# TK106_MIDI.net
KiCad netlist of a schematic drawn in Altium Designer
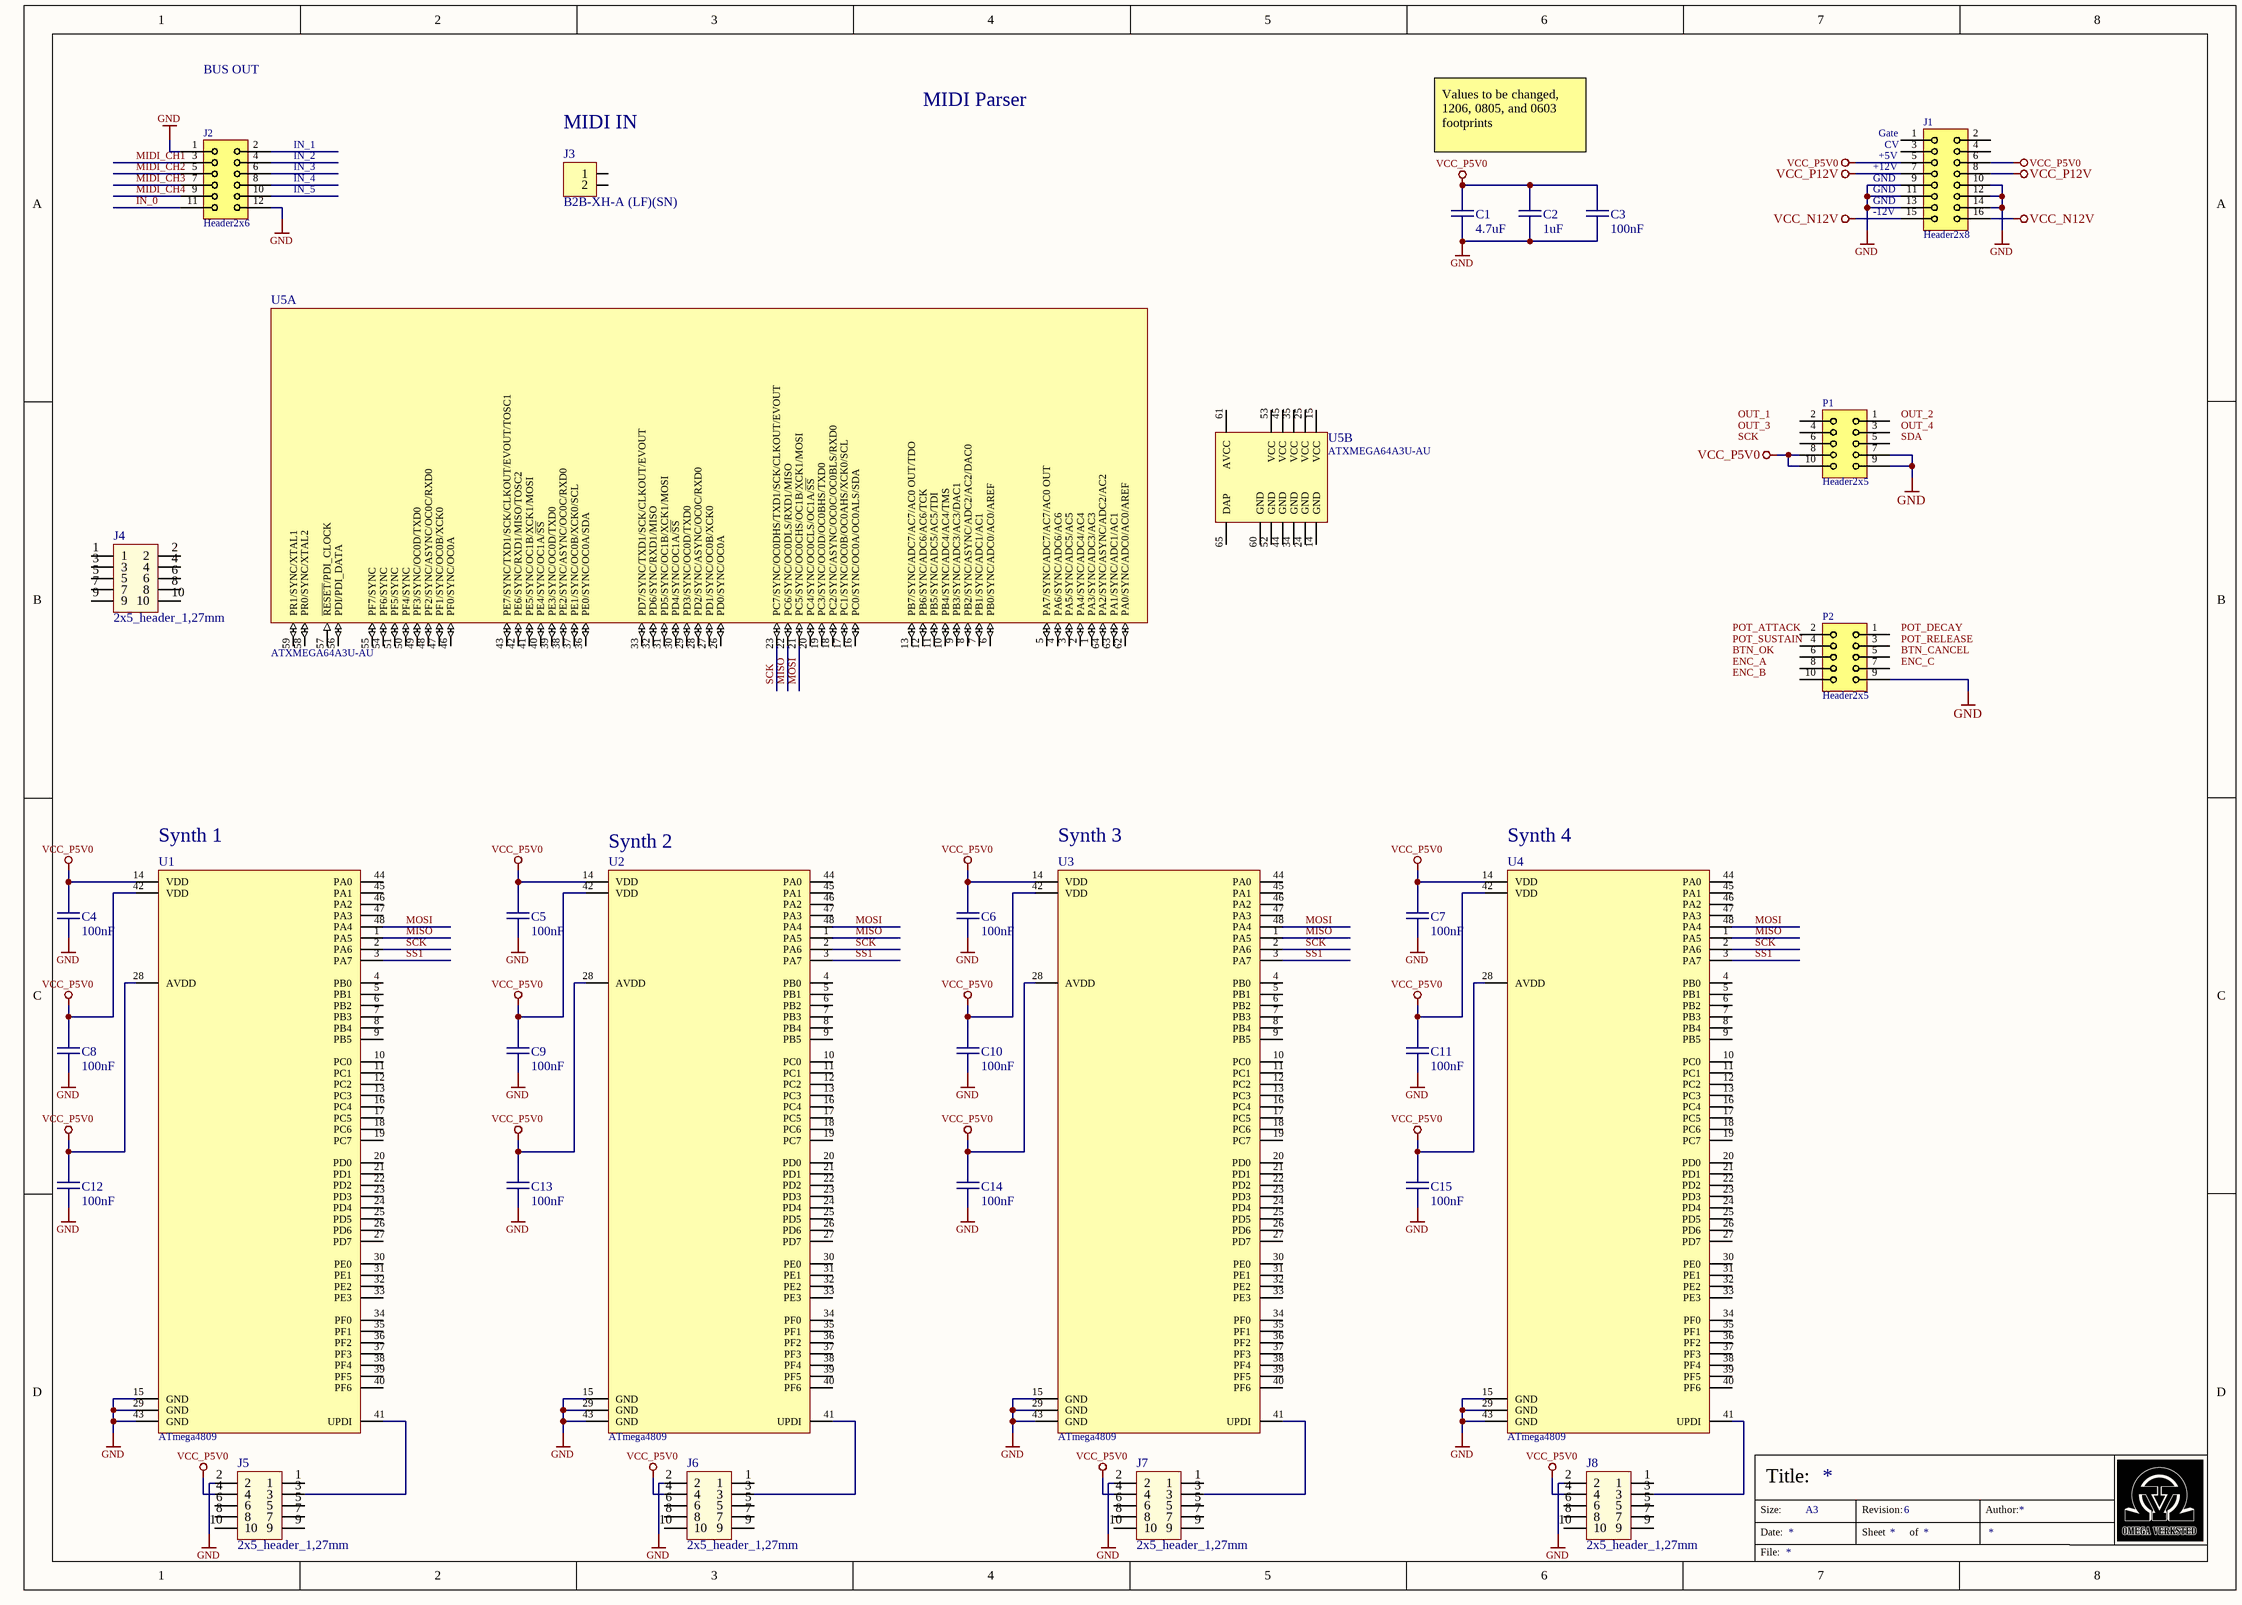
[diagram p0: TK106_MIDI.SchDoc]

(export (version "E")
  (design (tool "Eeschema 10.0.6"))
  (components
    (comp (ref "C1")
      (value "4.7uF")
      (footprint "CAPC1206(3216)170_N")
      (description "X7R 50V")
      (libsource (lib "OVLib") (part "CAP"))
    )
    (comp (ref "C2")
      (value "1uF")
      (footprint "CAPC0805(2012)100_N")
      (description "X7R 50V 10%")
      (libsource (lib "OVLib") (part "CAP"))
    )
    (comp (ref "C3")
      (value "100nF")
      (footprint "CAPC0603(1608)55_N")
      (description "X7R 50V 5%")
      (libsource (lib "OVLib") (part "CAP"))
    )
    (comp (ref "C4")
      (value "100nF")
      (footprint "CAPC0603(1608)55_N")
      (description "X7R 50V 5%")
      (libsource (lib "OVLib_64") (part "CAP"))
    )
    (comp (ref "C5")
      (value "100nF")
      (footprint "CAPC0603(1608)55_N")
      (description "X7R 50V 5%")
      (libsource (lib "OVLib_64") (part "CAP"))
    )
    (comp (ref "C6")
      (value "100nF")
      (footprint "CAPC0603(1608)55_N")
      (description "X7R 50V 5%")
      (libsource (lib "OVLib_64") (part "CAP"))
    )
    (comp (ref "C7")
      (value "100nF")
      (footprint "CAPC0603(1608)55_N")
      (description "X7R 50V 5%")
      (libsource (lib "OVLib_64") (part "CAP"))
    )
    (comp (ref "C8")
      (value "100nF")
      (footprint "CAPC0603(1608)55_N")
      (description "X7R 50V 5%")
      (libsource (lib "OVLib_64") (part "CAP"))
    )
    (comp (ref "C9")
      (value "100nF")
      (footprint "CAPC0603(1608)55_N")
      (description "X7R 50V 5%")
      (libsource (lib "OVLib_64") (part "CAP"))
    )
    (comp (ref "C10")
      (value "100nF")
      (footprint "CAPC0603(1608)55_N")
      (description "X7R 50V 5%")
      (libsource (lib "OVLib_64") (part "CAP"))
    )
    (comp (ref "C11")
      (value "100nF")
      (footprint "CAPC0603(1608)55_N")
      (description "X7R 50V 5%")
      (libsource (lib "OVLib_64") (part "CAP"))
    )
    (comp (ref "C12")
      (value "100nF")
      (footprint "CAPC0603(1608)55_N")
      (description "X7R 50V 5%")
      (libsource (lib "OVLib_64") (part "CAP"))
    )
    (comp (ref "C13")
      (value "100nF")
      (footprint "CAPC0603(1608)55_N")
      (description "X7R 50V 5%")
      (libsource (lib "OVLib_64") (part "CAP"))
    )
    (comp (ref "C14")
      (value "100nF")
      (footprint "CAPC0603(1608)55_N")
      (description "X7R 50V 5%")
      (libsource (lib "OVLib_64") (part "CAP"))
    )
    (comp (ref "C15")
      (value "100nF")
      (footprint "CAPC0603(1608)55_N")
      (description "X7R 50V 5%")
      (libsource (lib "OVLib_64") (part "CAP"))
    )
    (comp (ref "J1")
      (value "Header2x8")
      (footprint "HDRV16W64P254_2X8_Shrouded")
      (libsource (lib "OVLib_64") (part "Header2x8"))
    )
    (comp (ref "J2")
      (value "Header2x6")
      (footprint "HDRV12W64P254_2X6_Shrouded")
      (libsource (lib "OVLib_64") (part "Header2x6"))
    )
    (comp (ref "J3")
      (value "B2B-XH-A (LF)(SN)")
      (footprint "JST_2P")
      (libsource (lib "OVLib_64") (part "2PConnector"))
    )
    (comp (ref "J4")
      (value "2x5_header_1,27mm")
      (footprint "SMDHDRV10P127_2X5_615X330X560B")
      (libsource (lib "") (part "2x5_header_1,27mm_1"))
    )
    (comp (ref "J5")
      (value "2x5_header_1,27mm")
      (footprint "SMDHDRV10P127_2X5_615X330X560B")
      (libsource (lib "OVLib_64") (part "2x5_header_1,27mm"))
    )
    (comp (ref "J6")
      (value "2x5_header_1,27mm")
      (footprint "SMDHDRV10P127_2X5_615X330X560B")
      (libsource (lib "OVLib_64") (part "2x5_header_1,27mm"))
    )
    (comp (ref "J7")
      (value "2x5_header_1,27mm")
      (footprint "SMDHDRV10P127_2X5_615X330X560B")
      (libsource (lib "OVLib_64") (part "2x5_header_1,27mm"))
    )
    (comp (ref "J8")
      (value "2x5_header_1,27mm")
      (footprint "SMDHDRV10P127_2X5_615X330X560B")
      (libsource (lib "OVLib_64") (part "2x5_header_1,27mm"))
    )
    (comp (ref "P1")
      (value "Header2x5")
      (footprint "HDRV10W64P254_2X5_Female")
      (libsource (lib "OVLib_64") (part "Header2x5"))
    )
    (comp (ref "P2")
      (value "Header2x5")
      (footprint "HDRV10W64P254_2X5_Female")
      (libsource (lib "OVLib_64") (part "Header2x5"))
    )
    (comp (ref "U1")
      (value "ATmega4809")
      (footprint "TQFP50P900X900X120-48N")
      (libsource (lib "OVLib_64") (part "ATMEGA4809"))
    )
    (comp (ref "U2")
      (value "ATmega4809")
      (footprint "TQFP50P900X900X120-48N")
      (libsource (lib "OVLib_64") (part "ATMEGA4809"))
    )
    (comp (ref "U3")
      (value "ATmega4809")
      (footprint "TQFP50P900X900X120-48N")
      (libsource (lib "OVLib_64") (part "ATMEGA4809"))
    )
    (comp (ref "U4")
      (value "ATmega4809")
      (footprint "TQFP50P900X900X120-48N")
      (libsource (lib "OVLib_64") (part "ATMEGA4809"))
    )
    (comp (ref "U5")
      (value "ATXMEGA64A3U-AU")
      (footprint "TQFP64")
      (libsource (lib "OVLib_64") (part "ATXMEGA-64A3"))
    )
  )
  (nets
    (net (code "6") (name "/IN_0") (class "Default")
      (node (ref "J2") (pin "11") (pinfunction "11_11") (pintype "passive"))
    )
    (net (code "7") (name "/MIDI_CH1") (class "Default")
      (node (ref "J2") (pin "3") (pinfunction "3_3") (pintype "passive"))
    )
    (net (code "8") (name "/MIDI_CH2") (class "Default")
      (node (ref "J2") (pin "5") (pinfunction "5_5") (pintype "passive"))
    )
    (net (code "9") (name "/MIDI_CH3") (class "Default")
      (node (ref "J2") (pin "7") (pinfunction "7_7") (pintype "passive"))
    )
    (net (code "10") (name "/MIDI_CH4") (class "Default")
      (node (ref "J2") (pin "9") (pinfunction "9_9") (pintype "passive"))
    )
    (net (code "11") (name "/MISO") (class "Default")
      (node (ref "U1") (pin "1") (pinfunction "PA5_1") (pintype "passive"))
      (node (ref "U2") (pin "1") (pinfunction "PA5_1") (pintype "passive"))
      (node (ref "U3") (pin "1") (pinfunction "PA5_1") (pintype "passive"))
      (node (ref "U4") (pin "1") (pinfunction "PA5_1") (pintype "passive"))
      (node (ref "U5") (pin "22") (pinfunction "PC6/SYNC/OC0DLS/RXD1/MISO_22") (pintype "bidirectional"))
    )
    (net (code "12") (name "/MOSI") (class "Default")
      (node (ref "U1") (pin "48") (pinfunction "PA4_48") (pintype "passive"))
      (node (ref "U2") (pin "48") (pinfunction "PA4_48") (pintype "passive"))
      (node (ref "U3") (pin "48") (pinfunction "PA4_48") (pintype "passive"))
      (node (ref "U4") (pin "48") (pinfunction "PA4_48") (pintype "passive"))
      (node (ref "U5") (pin "21") (pinfunction "PC5/SYNC/OC0CHS/OC1B/XCK1/MOSI_21") (pintype "bidirectional"))
    )
    (net (code "21") (name "/SCK") (class "Default")
      (node (ref "U1") (pin "2") (pinfunction "PA6_2") (pintype "passive"))
      (node (ref "U2") (pin "2") (pinfunction "PA6_2") (pintype "passive"))
      (node (ref "U3") (pin "2") (pinfunction "PA6_2") (pintype "passive"))
      (node (ref "U4") (pin "2") (pinfunction "PA6_2") (pintype "passive"))
      (node (ref "U5") (pin "23") (pinfunction "PC7/SYNC/OC0DHS/TXD1/SCK/CLKOUT/EVOUT_23") (pintype "bidirectional"))
    )
    (net (code "23") (name "/SS1") (class "Default")
      (node (ref "U1") (pin "3") (pinfunction "PA7_3") (pintype "passive"))
      (node (ref "U2") (pin "3") (pinfunction "PA7_3") (pintype "passive"))
      (node (ref "U3") (pin "3") (pinfunction "PA7_3") (pintype "passive"))
      (node (ref "U4") (pin "3") (pinfunction "PA7_3") (pintype "passive"))
    )
    (net (code "24") (name "GND") (class "Default")
      (node (ref "C1") (pin "1") (pinfunction "1_1") (pintype "passive"))
      (node (ref "C10") (pin "1") (pinfunction "1_1") (pintype "passive"))
      (node (ref "C11") (pin "1") (pinfunction "1_1") (pintype "passive"))
      (node (ref "C12") (pin "1") (pinfunction "1_1") (pintype "passive"))
      (node (ref "C13") (pin "1") (pinfunction "1_1") (pintype "passive"))
      (node (ref "C14") (pin "1") (pinfunction "1_1") (pintype "passive"))
      (node (ref "C15") (pin "1") (pinfunction "1_1") (pintype "passive"))
      (node (ref "C2") (pin "1") (pinfunction "1_1") (pintype "passive"))
      (node (ref "C3") (pin "1") (pinfunction "1_1") (pintype "passive"))
      (node (ref "C4") (pin "1") (pinfunction "1_1") (pintype "passive"))
      (node (ref "C5") (pin "1") (pinfunction "1_1") (pintype "passive"))
      (node (ref "C6") (pin "1") (pinfunction "1_1") (pintype "passive"))
      (node (ref "C7") (pin "1") (pinfunction "1_1") (pintype "passive"))
      (node (ref "C8") (pin "1") (pinfunction "1_1") (pintype "passive"))
      (node (ref "C9") (pin "1") (pinfunction "1_1") (pintype "passive"))
      (node (ref "J1") (pin "10") (pinfunction "10_10") (pintype "passive"))
      (node (ref "J1") (pin "11") (pinfunction "11_11") (pintype "passive"))
      (node (ref "J1") (pin "12") (pinfunction "12_12") (pintype "passive"))
      (node (ref "J1") (pin "13") (pinfunction "13_13") (pintype "passive"))
      (node (ref "J1") (pin "14") (pinfunction "14_14") (pintype "passive"))
      (node (ref "J1") (pin "9") (pinfunction "9_9") (pintype "passive"))
      (node (ref "J2") (pin "1") (pinfunction "1_1") (pintype "passive"))
      (node (ref "J2") (pin "12") (pinfunction "12_12") (pintype "passive"))
      (node (ref "J5") (pin "2") (pinfunction "2_2") (pintype "power_in"))
      (node (ref "J6") (pin "2") (pinfunction "2_2") (pintype "power_in"))
      (node (ref "J7") (pin "2") (pinfunction "2_2") (pintype "power_in"))
      (node (ref "J8") (pin "2") (pinfunction "2_2") (pintype "power_in"))
      (node (ref "P1") (pin "7") (pinfunction "7_7") (pintype "passive"))
      (node (ref "P1") (pin "9") (pinfunction "9_9") (pintype "passive"))
      (node (ref "P2") (pin "9") (pinfunction "9_9") (pintype "passive"))
      (node (ref "U1") (pin "15") (pinfunction "GND_15") (pintype "passive"))
      (node (ref "U1") (pin "29") (pinfunction "GND_29") (pintype "passive"))
      (node (ref "U1") (pin "43") (pinfunction "GND_43") (pintype "passive"))
      (node (ref "U2") (pin "15") (pinfunction "GND_15") (pintype "passive"))
      (node (ref "U2") (pin "29") (pinfunction "GND_29") (pintype "passive"))
      (node (ref "U2") (pin "43") (pinfunction "GND_43") (pintype "passive"))
      (node (ref "U3") (pin "15") (pinfunction "GND_15") (pintype "passive"))
      (node (ref "U3") (pin "29") (pinfunction "GND_29") (pintype "passive"))
      (node (ref "U3") (pin "43") (pinfunction "GND_43") (pintype "passive"))
      (node (ref "U4") (pin "15") (pinfunction "GND_15") (pintype "passive"))
      (node (ref "U4") (pin "29") (pinfunction "GND_29") (pintype "passive"))
      (node (ref "U4") (pin "43") (pinfunction "GND_43") (pintype "passive"))
    )
    (net (code "25") (name "Net-(U1-UPDI)") (class "Default")
      (node (ref "J5") (pin "3") (pinfunction "3_3") (pintype "power_in"))
      (node (ref "U1") (pin "41") (pinfunction "UPDI_41") (pintype "passive"))
    )
    (net (code "26") (name "Net-(U2-UPDI)") (class "Default")
      (node (ref "J6") (pin "3") (pinfunction "3_3") (pintype "power_in"))
      (node (ref "U2") (pin "41") (pinfunction "UPDI_41") (pintype "passive"))
    )
    (net (code "27") (name "Net-(U3-UPDI)") (class "Default")
      (node (ref "J7") (pin "3") (pinfunction "3_3") (pintype "power_in"))
      (node (ref "U3") (pin "41") (pinfunction "UPDI_41") (pintype "passive"))
    )
    (net (code "28") (name "Net-(U4-UPDI)") (class "Default")
      (node (ref "J8") (pin "3") (pinfunction "3_3") (pintype "power_in"))
      (node (ref "U4") (pin "41") (pinfunction "UPDI_41") (pintype "passive"))
    )
    (net (code "29") (name "VCC_N12V") (class "Default")
      (node (ref "J1") (pin "15") (pinfunction "15_15") (pintype "passive"))
      (node (ref "J1") (pin "16") (pinfunction "16_16") (pintype "passive"))
    )
    (net (code "30") (name "VCC_P5V0") (class "Default")
      (node (ref "C1") (pin "2") (pinfunction "2_2") (pintype "passive"))
      (node (ref "C10") (pin "2") (pinfunction "2_2") (pintype "passive"))
      (node (ref "C11") (pin "2") (pinfunction "2_2") (pintype "passive"))
      (node (ref "C12") (pin "2") (pinfunction "2_2") (pintype "passive"))
      (node (ref "C13") (pin "2") (pinfunction "2_2") (pintype "passive"))
      (node (ref "C14") (pin "2") (pinfunction "2_2") (pintype "passive"))
      (node (ref "C15") (pin "2") (pinfunction "2_2") (pintype "passive"))
      (node (ref "C2") (pin "2") (pinfunction "2_2") (pintype "passive"))
      (node (ref "C3") (pin "2") (pinfunction "2_2") (pintype "passive"))
      (node (ref "C4") (pin "2") (pinfunction "2_2") (pintype "passive"))
      (node (ref "C5") (pin "2") (pinfunction "2_2") (pintype "passive"))
      (node (ref "C6") (pin "2") (pinfunction "2_2") (pintype "passive"))
      (node (ref "C7") (pin "2") (pinfunction "2_2") (pintype "passive"))
      (node (ref "C8") (pin "2") (pinfunction "2_2") (pintype "passive"))
      (node (ref "C9") (pin "2") (pinfunction "2_2") (pintype "passive"))
      (node (ref "J1") (pin "5") (pinfunction "5_5") (pintype "passive"))
      (node (ref "J1") (pin "6") (pinfunction "6_6") (pintype "passive"))
      (node (ref "J5") (pin "4") (pinfunction "4_4") (pintype "power_in"))
      (node (ref "J6") (pin "4") (pinfunction "4_4") (pintype "power_in"))
      (node (ref "J7") (pin "4") (pinfunction "4_4") (pintype "power_in"))
      (node (ref "J8") (pin "4") (pinfunction "4_4") (pintype "power_in"))
      (node (ref "P1") (pin "10") (pinfunction "10_10") (pintype "passive"))
      (node (ref "P1") (pin "8") (pinfunction "8_8") (pintype "passive"))
      (node (ref "U1") (pin "14") (pinfunction "VDD_14") (pintype "passive"))
      (node (ref "U1") (pin "28") (pinfunction "AVDD_28") (pintype "passive"))
      (node (ref "U1") (pin "42") (pinfunction "VDD_42") (pintype "passive"))
      (node (ref "U2") (pin "14") (pinfunction "VDD_14") (pintype "passive"))
      (node (ref "U2") (pin "28") (pinfunction "AVDD_28") (pintype "passive"))
      (node (ref "U2") (pin "42") (pinfunction "VDD_42") (pintype "passive"))
      (node (ref "U3") (pin "14") (pinfunction "VDD_14") (pintype "passive"))
      (node (ref "U3") (pin "28") (pinfunction "AVDD_28") (pintype "passive"))
      (node (ref "U3") (pin "42") (pinfunction "VDD_42") (pintype "passive"))
      (node (ref "U4") (pin "14") (pinfunction "VDD_14") (pintype "passive"))
      (node (ref "U4") (pin "28") (pinfunction "AVDD_28") (pintype "passive"))
      (node (ref "U4") (pin "42") (pinfunction "VDD_42") (pintype "passive"))
    )
    (net (code "31") (name "VCC_P12V") (class "Default")
      (node (ref "J1") (pin "7") (pinfunction "7_7") (pintype "passive"))
      (node (ref "J1") (pin "8") (pinfunction "8_8") (pintype "passive"))
    )
    (net (code "32") (name "unconnected-(J1-Pad1)") (class "Default")
      (node (ref "J1") (pin "1") (pinfunction "1_1") (pintype "passive"))
    )
    (net (code "33") (name "unconnected-(J1-Pad2)") (class "Default")
      (node (ref "J1") (pin "2") (pinfunction "2_2") (pintype "passive"))
    )
    (net (code "34") (name "unconnected-(J1-Pad3)") (class "Default")
      (node (ref "J1") (pin "3") (pinfunction "3_3") (pintype "passive"))
    )
    (net (code "35") (name "unconnected-(J1-Pad4)") (class "Default")
      (node (ref "J1") (pin "4") (pinfunction "4_4") (pintype "passive"))
    )
    (net (code "36") (name "unconnected-(J2-Pad2)") (class "Default")
      (node (ref "J2") (pin "2") (pinfunction "2_2") (pintype "passive"))
    )
    (net (code "37") (name "unconnected-(J2-Pad4)") (class "Default")
      (node (ref "J2") (pin "4") (pinfunction "4_4") (pintype "passive"))
    )
    (net (code "38") (name "unconnected-(J2-Pad6)") (class "Default")
      (node (ref "J2") (pin "6") (pinfunction "6_6") (pintype "passive"))
    )
    (net (code "39") (name "unconnected-(J2-Pad8)") (class "Default")
      (node (ref "J2") (pin "8") (pinfunction "8_8") (pintype "passive"))
    )
    (net (code "40") (name "unconnected-(J2-Pad10)") (class "Default")
      (node (ref "J2") (pin "10") (pinfunction "10_10") (pintype "passive"))
    )
    (net (code "41") (name "unconnected-(J3-Pad1)") (class "Default")
      (node (ref "J3") (pin "1") (pinfunction "1_1") (pintype "passive"))
    )
    (net (code "42") (name "unconnected-(J3-Pad2)") (class "Default")
      (node (ref "J3") (pin "2") (pinfunction "2_2") (pintype "passive"))
    )
    (net (code "43") (name "unconnected-(J4-Pad1)") (class "Default")
      (node (ref "J4") (pin "1") (pinfunction "1_1") (pintype "power_in"))
    )
    (net (code "44") (name "unconnected-(J4-Pad2)") (class "Default")
      (node (ref "J4") (pin "2") (pinfunction "2_2") (pintype "power_in"))
    )
    (net (code "45") (name "unconnected-(J4-Pad3)") (class "Default")
      (node (ref "J4") (pin "3") (pinfunction "3_3") (pintype "power_in"))
    )
    (net (code "46") (name "unconnected-(J4-Pad4)") (class "Default")
      (node (ref "J4") (pin "4") (pinfunction "4_4") (pintype "power_in"))
    )
    (net (code "47") (name "unconnected-(J4-Pad5)") (class "Default")
      (node (ref "J4") (pin "5") (pinfunction "5_5") (pintype "power_in"))
    )
    (net (code "48") (name "unconnected-(J4-Pad6)") (class "Default")
      (node (ref "J4") (pin "6") (pinfunction "6_6") (pintype "power_in"))
    )
    (net (code "49") (name "unconnected-(J4-Pad7)") (class "Default")
      (node (ref "J4") (pin "7") (pinfunction "7_7") (pintype "power_in"))
    )
    (net (code "50") (name "unconnected-(J4-Pad8)") (class "Default")
      (node (ref "J4") (pin "8") (pinfunction "8_8") (pintype "power_in"))
    )
    (net (code "51") (name "unconnected-(J4-Pad9)") (class "Default")
      (node (ref "J4") (pin "9") (pinfunction "9_9") (pintype "power_in"))
    )
    (net (code "52") (name "unconnected-(J4-Pad10)") (class "Default")
      (node (ref "J4") (pin "10") (pinfunction "10_10") (pintype "power_in"))
    )
    (net (code "53") (name "unconnected-(J5-Pad1)") (class "Default")
      (node (ref "J5") (pin "1") (pinfunction "1_1") (pintype "power_in"))
    )
    (net (code "54") (name "unconnected-(J5-Pad5)") (class "Default")
      (node (ref "J5") (pin "5") (pinfunction "5_5") (pintype "power_in"))
    )
    (net (code "55") (name "unconnected-(J5-Pad6)") (class "Default")
      (node (ref "J5") (pin "6") (pinfunction "6_6") (pintype "power_in"))
    )
    (net (code "56") (name "unconnected-(J5-Pad7)") (class "Default")
      (node (ref "J5") (pin "7") (pinfunction "7_7") (pintype "power_in"))
    )
    (net (code "57") (name "unconnected-(J5-Pad8)") (class "Default")
      (node (ref "J5") (pin "8") (pinfunction "8_8") (pintype "power_in"))
    )
    (net (code "58") (name "unconnected-(J5-Pad9)") (class "Default")
      (node (ref "J5") (pin "9") (pinfunction "9_9") (pintype "power_in"))
    )
    (net (code "59") (name "unconnected-(J5-Pad10)") (class "Default")
      (node (ref "J5") (pin "10") (pinfunction "10_10") (pintype "power_in"))
    )
    (net (code "60") (name "unconnected-(J6-Pad1)") (class "Default")
      (node (ref "J6") (pin "1") (pinfunction "1_1") (pintype "power_in"))
    )
    (net (code "61") (name "unconnected-(J6-Pad5)") (class "Default")
      (node (ref "J6") (pin "5") (pinfunction "5_5") (pintype "power_in"))
    )
    (net (code "62") (name "unconnected-(J6-Pad6)") (class "Default")
      (node (ref "J6") (pin "6") (pinfunction "6_6") (pintype "power_in"))
    )
    (net (code "63") (name "unconnected-(J6-Pad7)") (class "Default")
      (node (ref "J6") (pin "7") (pinfunction "7_7") (pintype "power_in"))
    )
    (net (code "64") (name "unconnected-(J6-Pad8)") (class "Default")
      (node (ref "J6") (pin "8") (pinfunction "8_8") (pintype "power_in"))
    )
    (net (code "65") (name "unconnected-(J6-Pad9)") (class "Default")
      (node (ref "J6") (pin "9") (pinfunction "9_9") (pintype "power_in"))
    )
    (net (code "66") (name "unconnected-(J6-Pad10)") (class "Default")
      (node (ref "J6") (pin "10") (pinfunction "10_10") (pintype "power_in"))
    )
    (net (code "67") (name "unconnected-(J7-Pad1)") (class "Default")
      (node (ref "J7") (pin "1") (pinfunction "1_1") (pintype "power_in"))
    )
    (net (code "68") (name "unconnected-(J7-Pad5)") (class "Default")
      (node (ref "J7") (pin "5") (pinfunction "5_5") (pintype "power_in"))
    )
    (net (code "69") (name "unconnected-(J7-Pad6)") (class "Default")
      (node (ref "J7") (pin "6") (pinfunction "6_6") (pintype "power_in"))
    )
    (net (code "70") (name "unconnected-(J7-Pad7)") (class "Default")
      (node (ref "J7") (pin "7") (pinfunction "7_7") (pintype "power_in"))
    )
    (net (code "71") (name "unconnected-(J7-Pad8)") (class "Default")
      (node (ref "J7") (pin "8") (pinfunction "8_8") (pintype "power_in"))
    )
    (net (code "72") (name "unconnected-(J7-Pad9)") (class "Default")
      (node (ref "J7") (pin "9") (pinfunction "9_9") (pintype "power_in"))
    )
    (net (code "73") (name "unconnected-(J7-Pad10)") (class "Default")
      (node (ref "J7") (pin "10") (pinfunction "10_10") (pintype "power_in"))
    )
    (net (code "74") (name "unconnected-(J8-Pad1)") (class "Default")
      (node (ref "J8") (pin "1") (pinfunction "1_1") (pintype "power_in"))
    )
    (net (code "75") (name "unconnected-(J8-Pad5)") (class "Default")
      (node (ref "J8") (pin "5") (pinfunction "5_5") (pintype "power_in"))
    )
    (net (code "76") (name "unconnected-(J8-Pad6)") (class "Default")
      (node (ref "J8") (pin "6") (pinfunction "6_6") (pintype "power_in"))
    )
    (net (code "77") (name "unconnected-(J8-Pad7)") (class "Default")
      (node (ref "J8") (pin "7") (pinfunction "7_7") (pintype "power_in"))
    )
    (net (code "78") (name "unconnected-(J8-Pad8)") (class "Default")
      (node (ref "J8") (pin "8") (pinfunction "8_8") (pintype "power_in"))
    )
    (net (code "79") (name "unconnected-(J8-Pad9)") (class "Default")
      (node (ref "J8") (pin "9") (pinfunction "9_9") (pintype "power_in"))
    )
    (net (code "80") (name "unconnected-(J8-Pad10)") (class "Default")
      (node (ref "J8") (pin "10") (pinfunction "10_10") (pintype "power_in"))
    )
    (net (code "81") (name "unconnected-(P1-Pad1)") (class "Default")
      (node (ref "P1") (pin "1") (pinfunction "1_1") (pintype "passive"))
    )
    (net (code "82") (name "unconnected-(P1-Pad2)") (class "Default")
      (node (ref "P1") (pin "2") (pinfunction "2_2") (pintype "passive"))
    )
    (net (code "83") (name "unconnected-(P1-Pad3)") (class "Default")
      (node (ref "P1") (pin "3") (pinfunction "3_3") (pintype "passive"))
    )
    (net (code "84") (name "unconnected-(P1-Pad4)") (class "Default")
      (node (ref "P1") (pin "4") (pinfunction "4_4") (pintype "passive"))
    )
    (net (code "85") (name "unconnected-(P1-Pad5)") (class "Default")
      (node (ref "P1") (pin "5") (pinfunction "5_5") (pintype "passive"))
    )
    (net (code "86") (name "unconnected-(P1-Pad6)") (class "Default")
      (node (ref "P1") (pin "6") (pinfunction "6_6") (pintype "passive"))
    )
    (net (code "87") (name "unconnected-(P2-Pad1)") (class "Default")
      (node (ref "P2") (pin "1") (pinfunction "1_1") (pintype "passive"))
    )
    (net (code "88") (name "unconnected-(P2-Pad2)") (class "Default")
      (node (ref "P2") (pin "2") (pinfunction "2_2") (pintype "passive"))
    )
    (net (code "89") (name "unconnected-(P2-Pad3)") (class "Default")
      (node (ref "P2") (pin "3") (pinfunction "3_3") (pintype "passive"))
    )
    (net (code "90") (name "unconnected-(P2-Pad4)") (class "Default")
      (node (ref "P2") (pin "4") (pinfunction "4_4") (pintype "passive"))
    )
    (net (code "91") (name "unconnected-(P2-Pad5)") (class "Default")
      (node (ref "P2") (pin "5") (pinfunction "5_5") (pintype "passive"))
    )
    (net (code "92") (name "unconnected-(P2-Pad6)") (class "Default")
      (node (ref "P2") (pin "6") (pinfunction "6_6") (pintype "passive"))
    )
    (net (code "93") (name "unconnected-(P2-Pad7)") (class "Default")
      (node (ref "P2") (pin "7") (pinfunction "7_7") (pintype "passive"))
    )
    (net (code "94") (name "unconnected-(P2-Pad8)") (class "Default")
      (node (ref "P2") (pin "8") (pinfunction "8_8") (pintype "passive"))
    )
    (net (code "95") (name "unconnected-(P2-Pad10)") (class "Default")
      (node (ref "P2") (pin "10") (pinfunction "10_10") (pintype "passive"))
    )
    (net (code "96") (name "unconnected-(U1-PA0-Pad44)") (class "Default")
      (node (ref "U1") (pin "44") (pinfunction "PA0_44") (pintype "passive"))
    )
    (net (code "97") (name "unconnected-(U1-PA1-Pad45)") (class "Default")
      (node (ref "U1") (pin "45") (pinfunction "PA1_45") (pintype "passive"))
    )
    (net (code "98") (name "unconnected-(U1-PA2-Pad46)") (class "Default")
      (node (ref "U1") (pin "46") (pinfunction "PA2_46") (pintype "passive"))
    )
    (net (code "99") (name "unconnected-(U1-PA3-Pad47)") (class "Default")
      (node (ref "U1") (pin "47") (pinfunction "PA3_47") (pintype "passive"))
    )
    (net (code "100") (name "unconnected-(U1-PB0-Pad4)") (class "Default")
      (node (ref "U1") (pin "4") (pinfunction "PB0_4") (pintype "passive"))
    )
    (net (code "101") (name "unconnected-(U1-PB1-Pad5)") (class "Default")
      (node (ref "U1") (pin "5") (pinfunction "PB1_5") (pintype "passive"))
    )
    (net (code "102") (name "unconnected-(U1-PB2-Pad6)") (class "Default")
      (node (ref "U1") (pin "6") (pinfunction "PB2_6") (pintype "passive"))
    )
    (net (code "103") (name "unconnected-(U1-PB3-Pad7)") (class "Default")
      (node (ref "U1") (pin "7") (pinfunction "PB3_7") (pintype "passive"))
    )
    (net (code "104") (name "unconnected-(U1-PB4-Pad8)") (class "Default")
      (node (ref "U1") (pin "8") (pinfunction "PB4_8") (pintype "passive"))
    )
    (net (code "105") (name "unconnected-(U1-PB5-Pad9)") (class "Default")
      (node (ref "U1") (pin "9") (pinfunction "PB5_9") (pintype "passive"))
    )
    (net (code "106") (name "unconnected-(U1-PC0-Pad10)") (class "Default")
      (node (ref "U1") (pin "10") (pinfunction "PC0_10") (pintype "passive"))
    )
    (net (code "107") (name "unconnected-(U1-PC1-Pad11)") (class "Default")
      (node (ref "U1") (pin "11") (pinfunction "PC1_11") (pintype "passive"))
    )
    (net (code "108") (name "unconnected-(U1-PC2-Pad12)") (class "Default")
      (node (ref "U1") (pin "12") (pinfunction "PC2_12") (pintype "passive"))
    )
    (net (code "109") (name "unconnected-(U1-PC3-Pad13)") (class "Default")
      (node (ref "U1") (pin "13") (pinfunction "PC3_13") (pintype "passive"))
    )
    (net (code "110") (name "unconnected-(U1-PC4-Pad16)") (class "Default")
      (node (ref "U1") (pin "16") (pinfunction "PC4_16") (pintype "passive"))
    )
    (net (code "111") (name "unconnected-(U1-PC5-Pad17)") (class "Default")
      (node (ref "U1") (pin "17") (pinfunction "PC5_17") (pintype "passive"))
    )
    (net (code "112") (name "unconnected-(U1-PC6-Pad18)") (class "Default")
      (node (ref "U1") (pin "18") (pinfunction "PC6_18") (pintype "passive"))
    )
    (net (code "113") (name "unconnected-(U1-PC7-Pad19)") (class "Default")
      (node (ref "U1") (pin "19") (pinfunction "PC7_19") (pintype "passive"))
    )
    (net (code "114") (name "unconnected-(U1-PD0-Pad20)") (class "Default")
      (node (ref "U1") (pin "20") (pinfunction "PD0_20") (pintype "passive"))
    )
    (net (code "115") (name "unconnected-(U1-PD1-Pad21)") (class "Default")
      (node (ref "U1") (pin "21") (pinfunction "PD1_21") (pintype "passive"))
    )
    (net (code "116") (name "unconnected-(U1-PD2-Pad22)") (class "Default")
      (node (ref "U1") (pin "22") (pinfunction "PD2_22") (pintype "passive"))
    )
    (net (code "117") (name "unconnected-(U1-PD3-Pad23)") (class "Default")
      (node (ref "U1") (pin "23") (pinfunction "PD3_23") (pintype "passive"))
    )
    (net (code "118") (name "unconnected-(U1-PD4-Pad24)") (class "Default")
      (node (ref "U1") (pin "24") (pinfunction "PD4_24") (pintype "passive"))
    )
    (net (code "119") (name "unconnected-(U1-PD5-Pad25)") (class "Default")
      (node (ref "U1") (pin "25") (pinfunction "PD5_25") (pintype "passive"))
    )
    (net (code "120") (name "unconnected-(U1-PD6-Pad26)") (class "Default")
      (node (ref "U1") (pin "26") (pinfunction "PD6_26") (pintype "passive"))
    )
    (net (code "121") (name "unconnected-(U1-PD7-Pad27)") (class "Default")
      (node (ref "U1") (pin "27") (pinfunction "PD7_27") (pintype "passive"))
    )
    (net (code "122") (name "unconnected-(U1-PE0-Pad30)") (class "Default")
      (node (ref "U1") (pin "30") (pinfunction "PE0_30") (pintype "passive"))
    )
    (net (code "123") (name "unconnected-(U1-PE1-Pad31)") (class "Default")
      (node (ref "U1") (pin "31") (pinfunction "PE1_31") (pintype "passive"))
    )
    (net (code "124") (name "unconnected-(U1-PE2-Pad32)") (class "Default")
      (node (ref "U1") (pin "32") (pinfunction "PE2_32") (pintype "passive"))
    )
    (net (code "125") (name "unconnected-(U1-PE3-Pad33)") (class "Default")
      (node (ref "U1") (pin "33") (pinfunction "PE3_33") (pintype "passive"))
    )
    (net (code "126") (name "unconnected-(U1-PF0-Pad34)") (class "Default")
      (node (ref "U1") (pin "34") (pinfunction "PF0_34") (pintype "passive"))
    )
    (net (code "127") (name "unconnected-(U1-PF1-Pad35)") (class "Default")
      (node (ref "U1") (pin "35") (pinfunction "PF1_35") (pintype "passive"))
    )
    (net (code "128") (name "unconnected-(U1-PF2-Pad36)") (class "Default")
      (node (ref "U1") (pin "36") (pinfunction "PF2_36") (pintype "passive"))
    )
    (net (code "129") (name "unconnected-(U1-PF3-Pad37)") (class "Default")
      (node (ref "U1") (pin "37") (pinfunction "PF3_37") (pintype "passive"))
    )
    (net (code "130") (name "unconnected-(U1-PF4-Pad38)") (class "Default")
      (node (ref "U1") (pin "38") (pinfunction "PF4_38") (pintype "passive"))
    )
    (net (code "131") (name "unconnected-(U1-PF5-Pad39)") (class "Default")
      (node (ref "U1") (pin "39") (pinfunction "PF5_39") (pintype "passive"))
    )
    (net (code "132") (name "unconnected-(U1-PF6-Pad40)") (class "Default")
      (node (ref "U1") (pin "40") (pinfunction "PF6_40") (pintype "passive"))
    )
    (net (code "133") (name "unconnected-(U2-PA0-Pad44)") (class "Default")
      (node (ref "U2") (pin "44") (pinfunction "PA0_44") (pintype "passive"))
    )
    (net (code "134") (name "unconnected-(U2-PA1-Pad45)") (class "Default")
      (node (ref "U2") (pin "45") (pinfunction "PA1_45") (pintype "passive"))
    )
    (net (code "135") (name "unconnected-(U2-PA2-Pad46)") (class "Default")
      (node (ref "U2") (pin "46") (pinfunction "PA2_46") (pintype "passive"))
    )
    (net (code "136") (name "unconnected-(U2-PA3-Pad47)") (class "Default")
      (node (ref "U2") (pin "47") (pinfunction "PA3_47") (pintype "passive"))
    )
    (net (code "137") (name "unconnected-(U2-PB0-Pad4)") (class "Default")
      (node (ref "U2") (pin "4") (pinfunction "PB0_4") (pintype "passive"))
    )
    (net (code "138") (name "unconnected-(U2-PB1-Pad5)") (class "Default")
      (node (ref "U2") (pin "5") (pinfunction "PB1_5") (pintype "passive"))
    )
    (net (code "139") (name "unconnected-(U2-PB2-Pad6)") (class "Default")
      (node (ref "U2") (pin "6") (pinfunction "PB2_6") (pintype "passive"))
    )
    (net (code "140") (name "unconnected-(U2-PB3-Pad7)") (class "Default")
      (node (ref "U2") (pin "7") (pinfunction "PB3_7") (pintype "passive"))
    )
    (net (code "141") (name "unconnected-(U2-PB4-Pad8)") (class "Default")
      (node (ref "U2") (pin "8") (pinfunction "PB4_8") (pintype "passive"))
    )
    (net (code "142") (name "unconnected-(U2-PB5-Pad9)") (class "Default")
      (node (ref "U2") (pin "9") (pinfunction "PB5_9") (pintype "passive"))
    )
    (net (code "143") (name "unconnected-(U2-PC0-Pad10)") (class "Default")
      (node (ref "U2") (pin "10") (pinfunction "PC0_10") (pintype "passive"))
    )
    (net (code "144") (name "unconnected-(U2-PC1-Pad11)") (class "Default")
      (node (ref "U2") (pin "11") (pinfunction "PC1_11") (pintype "passive"))
    )
    (net (code "145") (name "unconnected-(U2-PC2-Pad12)") (class "Default")
      (node (ref "U2") (pin "12") (pinfunction "PC2_12") (pintype "passive"))
    )
    (net (code "146") (name "unconnected-(U2-PC3-Pad13)") (class "Default")
      (node (ref "U2") (pin "13") (pinfunction "PC3_13") (pintype "passive"))
    )
    (net (code "147") (name "unconnected-(U2-PC4-Pad16)") (class "Default")
      (node (ref "U2") (pin "16") (pinfunction "PC4_16") (pintype "passive"))
    )
    (net (code "148") (name "unconnected-(U2-PC5-Pad17)") (class "Default")
      (node (ref "U2") (pin "17") (pinfunction "PC5_17") (pintype "passive"))
    )
    (net (code "149") (name "unconnected-(U2-PC6-Pad18)") (class "Default")
      (node (ref "U2") (pin "18") (pinfunction "PC6_18") (pintype "passive"))
    )
    (net (code "150") (name "unconnected-(U2-PC7-Pad19)") (class "Default")
      (node (ref "U2") (pin "19") (pinfunction "PC7_19") (pintype "passive"))
    )
    (net (code "151") (name "unconnected-(U2-PD0-Pad20)") (class "Default")
      (node (ref "U2") (pin "20") (pinfunction "PD0_20") (pintype "passive"))
    )
    (net (code "152") (name "unconnected-(U2-PD1-Pad21)") (class "Default")
      (node (ref "U2") (pin "21") (pinfunction "PD1_21") (pintype "passive"))
    )
    (net (code "153") (name "unconnected-(U2-PD2-Pad22)") (class "Default")
      (node (ref "U2") (pin "22") (pinfunction "PD2_22") (pintype "passive"))
    )
    (net (code "154") (name "unconnected-(U2-PD3-Pad23)") (class "Default")
      (node (ref "U2") (pin "23") (pinfunction "PD3_23") (pintype "passive"))
    )
    (net (code "155") (name "unconnected-(U2-PD4-Pad24)") (class "Default")
      (node (ref "U2") (pin "24") (pinfunction "PD4_24") (pintype "passive"))
    )
    (net (code "156") (name "unconnected-(U2-PD5-Pad25)") (class "Default")
      (node (ref "U2") (pin "25") (pinfunction "PD5_25") (pintype "passive"))
    )
    (net (code "157") (name "unconnected-(U2-PD6-Pad26)") (class "Default")
      (node (ref "U2") (pin "26") (pinfunction "PD6_26") (pintype "passive"))
    )
    (net (code "158") (name "unconnected-(U2-PD7-Pad27)") (class "Default")
      (node (ref "U2") (pin "27") (pinfunction "PD7_27") (pintype "passive"))
    )
    (net (code "159") (name "unconnected-(U2-PE0-Pad30)") (class "Default")
      (node (ref "U2") (pin "30") (pinfunction "PE0_30") (pintype "passive"))
    )
    (net (code "160") (name "unconnected-(U2-PE1-Pad31)") (class "Default")
      (node (ref "U2") (pin "31") (pinfunction "PE1_31") (pintype "passive"))
    )
    (net (code "161") (name "unconnected-(U2-PE2-Pad32)") (class "Default")
      (node (ref "U2") (pin "32") (pinfunction "PE2_32") (pintype "passive"))
    )
    (net (code "162") (name "unconnected-(U2-PE3-Pad33)") (class "Default")
      (node (ref "U2") (pin "33") (pinfunction "PE3_33") (pintype "passive"))
    )
    (net (code "163") (name "unconnected-(U2-PF0-Pad34)") (class "Default")
      (node (ref "U2") (pin "34") (pinfunction "PF0_34") (pintype "passive"))
    )
    (net (code "164") (name "unconnected-(U2-PF1-Pad35)") (class "Default")
      (node (ref "U2") (pin "35") (pinfunction "PF1_35") (pintype "passive"))
    )
    (net (code "165") (name "unconnected-(U2-PF2-Pad36)") (class "Default")
      (node (ref "U2") (pin "36") (pinfunction "PF2_36") (pintype "passive"))
    )
    (net (code "166") (name "unconnected-(U2-PF3-Pad37)") (class "Default")
      (node (ref "U2") (pin "37") (pinfunction "PF3_37") (pintype "passive"))
    )
    (net (code "167") (name "unconnected-(U2-PF4-Pad38)") (class "Default")
      (node (ref "U2") (pin "38") (pinfunction "PF4_38") (pintype "passive"))
    )
    (net (code "168") (name "unconnected-(U2-PF5-Pad39)") (class "Default")
      (node (ref "U2") (pin "39") (pinfunction "PF5_39") (pintype "passive"))
    )
    (net (code "169") (name "unconnected-(U2-PF6-Pad40)") (class "Default")
      (node (ref "U2") (pin "40") (pinfunction "PF6_40") (pintype "passive"))
    )
    (net (code "170") (name "unconnected-(U3-PA0-Pad44)") (class "Default")
      (node (ref "U3") (pin "44") (pinfunction "PA0_44") (pintype "passive"))
    )
    (net (code "171") (name "unconnected-(U3-PA1-Pad45)") (class "Default")
      (node (ref "U3") (pin "45") (pinfunction "PA1_45") (pintype "passive"))
    )
    (net (code "172") (name "unconnected-(U3-PA2-Pad46)") (class "Default")
      (node (ref "U3") (pin "46") (pinfunction "PA2_46") (pintype "passive"))
    )
    (net (code "173") (name "unconnected-(U3-PA3-Pad47)") (class "Default")
      (node (ref "U3") (pin "47") (pinfunction "PA3_47") (pintype "passive"))
    )
    (net (code "174") (name "unconnected-(U3-PB0-Pad4)") (class "Default")
      (node (ref "U3") (pin "4") (pinfunction "PB0_4") (pintype "passive"))
    )
    (net (code "175") (name "unconnected-(U3-PB1-Pad5)") (class "Default")
      (node (ref "U3") (pin "5") (pinfunction "PB1_5") (pintype "passive"))
    )
    (net (code "176") (name "unconnected-(U3-PB2-Pad6)") (class "Default")
      (node (ref "U3") (pin "6") (pinfunction "PB2_6") (pintype "passive"))
    )
    (net (code "177") (name "unconnected-(U3-PB3-Pad7)") (class "Default")
      (node (ref "U3") (pin "7") (pinfunction "PB3_7") (pintype "passive"))
    )
    (net (code "178") (name "unconnected-(U3-PB4-Pad8)") (class "Default")
      (node (ref "U3") (pin "8") (pinfunction "PB4_8") (pintype "passive"))
    )
    (net (code "179") (name "unconnected-(U3-PB5-Pad9)") (class "Default")
      (node (ref "U3") (pin "9") (pinfunction "PB5_9") (pintype "passive"))
    )
    (net (code "180") (name "unconnected-(U3-PC0-Pad10)") (class "Default")
      (node (ref "U3") (pin "10") (pinfunction "PC0_10") (pintype "passive"))
    )
    (net (code "181") (name "unconnected-(U3-PC1-Pad11)") (class "Default")
      (node (ref "U3") (pin "11") (pinfunction "PC1_11") (pintype "passive"))
    )
    (net (code "182") (name "unconnected-(U3-PC2-Pad12)") (class "Default")
      (node (ref "U3") (pin "12") (pinfunction "PC2_12") (pintype "passive"))
    )
    (net (code "183") (name "unconnected-(U3-PC3-Pad13)") (class "Default")
      (node (ref "U3") (pin "13") (pinfunction "PC3_13") (pintype "passive"))
    )
    (net (code "184") (name "unconnected-(U3-PC4-Pad16)") (class "Default")
      (node (ref "U3") (pin "16") (pinfunction "PC4_16") (pintype "passive"))
    )
    (net (code "185") (name "unconnected-(U3-PC5-Pad17)") (class "Default")
      (node (ref "U3") (pin "17") (pinfunction "PC5_17") (pintype "passive"))
    )
    (net (code "186") (name "unconnected-(U3-PC6-Pad18)") (class "Default")
      (node (ref "U3") (pin "18") (pinfunction "PC6_18") (pintype "passive"))
    )
    (net (code "187") (name "unconnected-(U3-PC7-Pad19)") (class "Default")
      (node (ref "U3") (pin "19") (pinfunction "PC7_19") (pintype "passive"))
    )
    (net (code "188") (name "unconnected-(U3-PD0-Pad20)") (class "Default")
      (node (ref "U3") (pin "20") (pinfunction "PD0_20") (pintype "passive"))
    )
    (net (code "189") (name "unconnected-(U3-PD1-Pad21)") (class "Default")
      (node (ref "U3") (pin "21") (pinfunction "PD1_21") (pintype "passive"))
    )
    (net (code "190") (name "unconnected-(U3-PD2-Pad22)") (class "Default")
      (node (ref "U3") (pin "22") (pinfunction "PD2_22") (pintype "passive"))
    )
    (net (code "191") (name "unconnected-(U3-PD3-Pad23)") (class "Default")
      (node (ref "U3") (pin "23") (pinfunction "PD3_23") (pintype "passive"))
    )
    (net (code "192") (name "unconnected-(U3-PD4-Pad24)") (class "Default")
      (node (ref "U3") (pin "24") (pinfunction "PD4_24") (pintype "passive"))
    )
    (net (code "193") (name "unconnected-(U3-PD5-Pad25)") (class "Default")
      (node (ref "U3") (pin "25") (pinfunction "PD5_25") (pintype "passive"))
    )
    (net (code "194") (name "unconnected-(U3-PD6-Pad26)") (class "Default")
      (node (ref "U3") (pin "26") (pinfunction "PD6_26") (pintype "passive"))
    )
    (net (code "195") (name "unconnected-(U3-PD7-Pad27)") (class "Default")
      (node (ref "U3") (pin "27") (pinfunction "PD7_27") (pintype "passive"))
    )
    (net (code "196") (name "unconnected-(U3-PE0-Pad30)") (class "Default")
      (node (ref "U3") (pin "30") (pinfunction "PE0_30") (pintype "passive"))
    )
    (net (code "197") (name "unconnected-(U3-PE1-Pad31)") (class "Default")
      (node (ref "U3") (pin "31") (pinfunction "PE1_31") (pintype "passive"))
    )
    (net (code "198") (name "unconnected-(U3-PE2-Pad32)") (class "Default")
      (node (ref "U3") (pin "32") (pinfunction "PE2_32") (pintype "passive"))
    )
    (net (code "199") (name "unconnected-(U3-PE3-Pad33)") (class "Default")
      (node (ref "U3") (pin "33") (pinfunction "PE3_33") (pintype "passive"))
    )
    (net (code "200") (name "unconnected-(U3-PF0-Pad34)") (class "Default")
      (node (ref "U3") (pin "34") (pinfunction "PF0_34") (pintype "passive"))
    )
    (net (code "201") (name "unconnected-(U3-PF1-Pad35)") (class "Default")
      (node (ref "U3") (pin "35") (pinfunction "PF1_35") (pintype "passive"))
    )
    (net (code "202") (name "unconnected-(U3-PF2-Pad36)") (class "Default")
      (node (ref "U3") (pin "36") (pinfunction "PF2_36") (pintype "passive"))
    )
    (net (code "203") (name "unconnected-(U3-PF3-Pad37)") (class "Default")
      (node (ref "U3") (pin "37") (pinfunction "PF3_37") (pintype "passive"))
    )
    (net (code "204") (name "unconnected-(U3-PF4-Pad38)") (class "Default")
      (node (ref "U3") (pin "38") (pinfunction "PF4_38") (pintype "passive"))
    )
    (net (code "205") (name "unconnected-(U3-PF5-Pad39)") (class "Default")
      (node (ref "U3") (pin "39") (pinfunction "PF5_39") (pintype "passive"))
    )
    (net (code "206") (name "unconnected-(U3-PF6-Pad40)") (class "Default")
      (node (ref "U3") (pin "40") (pinfunction "PF6_40") (pintype "passive"))
    )
    (net (code "207") (name "unconnected-(U4-PA0-Pad44)") (class "Default")
      (node (ref "U4") (pin "44") (pinfunction "PA0_44") (pintype "passive"))
    )
    (net (code "208") (name "unconnected-(U4-PA1-Pad45)") (class "Default")
      (node (ref "U4") (pin "45") (pinfunction "PA1_45") (pintype "passive"))
    )
    (net (code "209") (name "unconnected-(U4-PA2-Pad46)") (class "Default")
      (node (ref "U4") (pin "46") (pinfunction "PA2_46") (pintype "passive"))
    )
    (net (code "210") (name "unconnected-(U4-PA3-Pad47)") (class "Default")
      (node (ref "U4") (pin "47") (pinfunction "PA3_47") (pintype "passive"))
    )
    (net (code "211") (name "unconnected-(U4-PB0-Pad4)") (class "Default")
      (node (ref "U4") (pin "4") (pinfunction "PB0_4") (pintype "passive"))
    )
    (net (code "212") (name "unconnected-(U4-PB1-Pad5)") (class "Default")
      (node (ref "U4") (pin "5") (pinfunction "PB1_5") (pintype "passive"))
    )
    (net (code "213") (name "unconnected-(U4-PB2-Pad6)") (class "Default")
      (node (ref "U4") (pin "6") (pinfunction "PB2_6") (pintype "passive"))
    )
    (net (code "214") (name "unconnected-(U4-PB3-Pad7)") (class "Default")
      (node (ref "U4") (pin "7") (pinfunction "PB3_7") (pintype "passive"))
    )
    (net (code "215") (name "unconnected-(U4-PB4-Pad8)") (class "Default")
      (node (ref "U4") (pin "8") (pinfunction "PB4_8") (pintype "passive"))
    )
    (net (code "216") (name "unconnected-(U4-PB5-Pad9)") (class "Default")
      (node (ref "U4") (pin "9") (pinfunction "PB5_9") (pintype "passive"))
    )
    (net (code "217") (name "unconnected-(U4-PC0-Pad10)") (class "Default")
      (node (ref "U4") (pin "10") (pinfunction "PC0_10") (pintype "passive"))
    )
    (net (code "218") (name "unconnected-(U4-PC1-Pad11)") (class "Default")
      (node (ref "U4") (pin "11") (pinfunction "PC1_11") (pintype "passive"))
    )
    (net (code "219") (name "unconnected-(U4-PC2-Pad12)") (class "Default")
      (node (ref "U4") (pin "12") (pinfunction "PC2_12") (pintype "passive"))
    )
    (net (code "220") (name "unconnected-(U4-PC3-Pad13)") (class "Default")
      (node (ref "U4") (pin "13") (pinfunction "PC3_13") (pintype "passive"))
    )
    (net (code "221") (name "unconnected-(U4-PC4-Pad16)") (class "Default")
      (node (ref "U4") (pin "16") (pinfunction "PC4_16") (pintype "passive"))
    )
    (net (code "222") (name "unconnected-(U4-PC5-Pad17)") (class "Default")
      (node (ref "U4") (pin "17") (pinfunction "PC5_17") (pintype "passive"))
    )
    (net (code "223") (name "unconnected-(U4-PC6-Pad18)") (class "Default")
      (node (ref "U4") (pin "18") (pinfunction "PC6_18") (pintype "passive"))
    )
    (net (code "224") (name "unconnected-(U4-PC7-Pad19)") (class "Default")
      (node (ref "U4") (pin "19") (pinfunction "PC7_19") (pintype "passive"))
    )
    (net (code "225") (name "unconnected-(U4-PD0-Pad20)") (class "Default")
      (node (ref "U4") (pin "20") (pinfunction "PD0_20") (pintype "passive"))
    )
    (net (code "226") (name "unconnected-(U4-PD1-Pad21)") (class "Default")
      (node (ref "U4") (pin "21") (pinfunction "PD1_21") (pintype "passive"))
    )
    (net (code "227") (name "unconnected-(U4-PD2-Pad22)") (class "Default")
      (node (ref "U4") (pin "22") (pinfunction "PD2_22") (pintype "passive"))
    )
    (net (code "228") (name "unconnected-(U4-PD3-Pad23)") (class "Default")
      (node (ref "U4") (pin "23") (pinfunction "PD3_23") (pintype "passive"))
    )
    (net (code "229") (name "unconnected-(U4-PD4-Pad24)") (class "Default")
      (node (ref "U4") (pin "24") (pinfunction "PD4_24") (pintype "passive"))
    )
    (net (code "230") (name "unconnected-(U4-PD5-Pad25)") (class "Default")
      (node (ref "U4") (pin "25") (pinfunction "PD5_25") (pintype "passive"))
    )
    (net (code "231") (name "unconnected-(U4-PD6-Pad26)") (class "Default")
      (node (ref "U4") (pin "26") (pinfunction "PD6_26") (pintype "passive"))
    )
    (net (code "232") (name "unconnected-(U4-PD7-Pad27)") (class "Default")
      (node (ref "U4") (pin "27") (pinfunction "PD7_27") (pintype "passive"))
    )
    (net (code "233") (name "unconnected-(U4-PE0-Pad30)") (class "Default")
      (node (ref "U4") (pin "30") (pinfunction "PE0_30") (pintype "passive"))
    )
    (net (code "234") (name "unconnected-(U4-PE1-Pad31)") (class "Default")
      (node (ref "U4") (pin "31") (pinfunction "PE1_31") (pintype "passive"))
    )
    (net (code "235") (name "unconnected-(U4-PE2-Pad32)") (class "Default")
      (node (ref "U4") (pin "32") (pinfunction "PE2_32") (pintype "passive"))
    )
    (net (code "236") (name "unconnected-(U4-PE3-Pad33)") (class "Default")
      (node (ref "U4") (pin "33") (pinfunction "PE3_33") (pintype "passive"))
    )
    (net (code "237") (name "unconnected-(U4-PF0-Pad34)") (class "Default")
      (node (ref "U4") (pin "34") (pinfunction "PF0_34") (pintype "passive"))
    )
    (net (code "238") (name "unconnected-(U4-PF1-Pad35)") (class "Default")
      (node (ref "U4") (pin "35") (pinfunction "PF1_35") (pintype "passive"))
    )
    (net (code "239") (name "unconnected-(U4-PF2-Pad36)") (class "Default")
      (node (ref "U4") (pin "36") (pinfunction "PF2_36") (pintype "passive"))
    )
    (net (code "240") (name "unconnected-(U4-PF3-Pad37)") (class "Default")
      (node (ref "U4") (pin "37") (pinfunction "PF3_37") (pintype "passive"))
    )
    (net (code "241") (name "unconnected-(U4-PF4-Pad38)") (class "Default")
      (node (ref "U4") (pin "38") (pinfunction "PF4_38") (pintype "passive"))
    )
    (net (code "242") (name "unconnected-(U4-PF5-Pad39)") (class "Default")
      (node (ref "U4") (pin "39") (pinfunction "PF5_39") (pintype "passive"))
    )
    (net (code "243") (name "unconnected-(U4-PF6-Pad40)") (class "Default")
      (node (ref "U4") (pin "40") (pinfunction "PF6_40") (pintype "passive"))
    )
    (net (code "244") (name "unconnected-(U5A-PA0{slash}SYNC{slash}ADC0{slash}AC0{slash}AREF-Pad62)") (class "Default")
      (node (ref "U5") (pin "62") (pinfunction "PA0/SYNC/ADC0/AC0/AREF_62") (pintype "bidirectional"))
    )
    (net (code "245") (name "unconnected-(U5A-PA1{slash}SYNC{slash}ADC1{slash}AC1-Pad63)") (class "Default")
      (node (ref "U5") (pin "63") (pinfunction "PA1/SYNC/ADC1/AC1_63") (pintype "bidirectional"))
    )
    (net (code "246") (name "unconnected-(U5A-PA2{slash}SYNC{slash}ASYNC{slash}ADC2{slash}AC2-Pad64)") (class "Default")
      (node (ref "U5") (pin "64") (pinfunction "PA2/SYNC/ASYNC/ADC2/AC2_64") (pintype "bidirectional"))
    )
    (net (code "247") (name "unconnected-(U5A-PA3{slash}SYNC{slash}ADC3{slash}AC3-Pad1)") (class "Default")
      (node (ref "U5") (pin "1") (pinfunction "PA3/SYNC/ADC3/AC3_1") (pintype "bidirectional"))
    )
    (net (code "248") (name "unconnected-(U5A-PA4{slash}SYNC{slash}ADC4{slash}AC4-Pad2)") (class "Default")
      (node (ref "U5") (pin "2") (pinfunction "PA4/SYNC/ADC4/AC4_2") (pintype "bidirectional"))
    )
    (net (code "249") (name "unconnected-(U5A-PA5{slash}SYNC{slash}ADC5{slash}AC5-Pad3)") (class "Default")
      (node (ref "U5") (pin "3") (pinfunction "PA5/SYNC/ADC5/AC5_3") (pintype "bidirectional"))
    )
    (net (code "250") (name "unconnected-(U5A-PA6{slash}SYNC{slash}ADC6{slash}AC6-Pad4)") (class "Default")
      (node (ref "U5") (pin "4") (pinfunction "PA6/SYNC/ADC6/AC6_4") (pintype "bidirectional"))
    )
    (net (code "251") (name "unconnected-(U5A-PA7{slash}SYNC{slash}ADC7{slash}AC7{slash}AC0_OUT-Pad5)") (class "Default")
      (node (ref "U5") (pin "5") (pinfunction "PA7/SYNC/ADC7/AC7/AC0_OUT_5") (pintype "bidirectional"))
    )
    (net (code "252") (name "unconnected-(U5A-PB0{slash}SYNC{slash}ADC0{slash}AC0{slash}AREF-Pad6)") (class "Default")
      (node (ref "U5") (pin "6") (pinfunction "PB0/SYNC/ADC0/AC0/AREF_6") (pintype "bidirectional"))
    )
    (net (code "253") (name "unconnected-(U5A-PB1{slash}SYNC{slash}ADC1{slash}AC1-Pad7)") (class "Default")
      (node (ref "U5") (pin "7") (pinfunction "PB1/SYNC/ADC1/AC1_7") (pintype "bidirectional"))
    )
    (net (code "254") (name "unconnected-(U5A-PB2{slash}SYNC{slash}ASYNC{slash}ADC2{slash}AC2{slash}DAC0-Pad8)") (class "Default")
      (node (ref "U5") (pin "8") (pinfunction "PB2/SYNC/ASYNC/ADC2/AC2/DAC0_8") (pintype "bidirectional"))
    )
    (net (code "255") (name "unconnected-(U5A-PB3{slash}SYNC{slash}ADC3{slash}AC3{slash}DAC1-Pad9)") (class "Default")
      (node (ref "U5") (pin "9") (pinfunction "PB3/SYNC/ADC3/AC3/DAC1_9") (pintype "bidirectional"))
    )
    (net (code "256") (name "unconnected-(U5A-PB4{slash}SYNC{slash}ADC4{slash}AC4{slash}TMS-Pad10)") (class "Default")
      (node (ref "U5") (pin "10") (pinfunction "PB4/SYNC/ADC4/AC4/TMS_10") (pintype "bidirectional"))
    )
    (net (code "257") (name "unconnected-(U5A-PB5{slash}SYNC{slash}ADC5{slash}AC5{slash}TDI-Pad11)") (class "Default")
      (node (ref "U5") (pin "11") (pinfunction "PB5/SYNC/ADC5/AC5/TDI_11") (pintype "bidirectional"))
    )
    (net (code "258") (name "unconnected-(U5A-PB6{slash}SYNC{slash}ADC6{slash}AC6{slash}TCK-Pad12)") (class "Default")
      (node (ref "U5") (pin "12") (pinfunction "PB6/SYNC/ADC6/AC6/TCK_12") (pintype "bidirectional"))
    )
    (net (code "259") (name "unconnected-(U5A-PB7{slash}SYNC{slash}ADC7{slash}AC7{slash}AC0_OUT{slash}TDO-Pad13)") (class "Default")
      (node (ref "U5") (pin "13") (pinfunction "PB7/SYNC/ADC7/AC7/AC0_OUT/TDO_13") (pintype "bidirectional"))
    )
    (net (code "260") (name "unconnected-(U5A-PC0{slash}SYNC{slash}OC0A{slash}OC0ALS{slash}SDA-Pad16)") (class "Default")
      (node (ref "U5") (pin "16") (pinfunction "PC0/SYNC/OC0A/OC0ALS/SDA_16") (pintype "bidirectional"))
    )
    (net (code "261") (name "unconnected-(U5A-PC1{slash}SYNC{slash}OC0B{slash}OC0AHS{slash}XCK0{slash}SCL-Pad17)") (class "Default")
      (node (ref "U5") (pin "17") (pinfunction "PC1/SYNC/OC0B/OC0AHS/XCK0/SCL_17") (pintype "bidirectional"))
    )
    (net (code "262") (name "unconnected-(U5A-PC2{slash}SYNC{slash}ASYNC{slash}OC0C{slash}OC0BLS{slash}RXD0-Pad18)") (class "Default")
      (node (ref "U5") (pin "18") (pinfunction "PC2/SYNC/ASYNC/OC0C/OC0BLS/RXD0_18") (pintype "bidirectional"))
    )
    (net (code "263") (name "unconnected-(U5A-PC3{slash}SYNC{slash}OC0D{slash}OC0BHS{slash}TXD0-Pad19)") (class "Default")
      (node (ref "U5") (pin "19") (pinfunction "PC3/SYNC/OC0D/OC0BHS/TXD0_19") (pintype "bidirectional"))
    )
    (net (code "264") (name "unconnected-(U5A-PC4{slash}SYNC{slash}OC0CLS{slash}OC1A{slash}~{SS}-Pad20)") (class "Default")
      (node (ref "U5") (pin "20") (pinfunction "PC4/SYNC/OC0CLS/OC1A/~{SS}_20") (pintype "bidirectional"))
    )
    (net (code "265") (name "unconnected-(U5A-PD0{slash}SYNC{slash}OC0A-Pad26)") (class "Default")
      (node (ref "U5") (pin "26") (pinfunction "PD0/SYNC/OC0A_26") (pintype "bidirectional"))
    )
    (net (code "266") (name "unconnected-(U5A-PD1{slash}SYNC{slash}OC0B{slash}XCK0-Pad27)") (class "Default")
      (node (ref "U5") (pin "27") (pinfunction "PD1/SYNC/OC0B/XCK0_27") (pintype "bidirectional"))
    )
    (net (code "267") (name "unconnected-(U5A-PD2{slash}SYNC{slash}ASYNC{slash}OC0C{slash}RXD0-Pad28)") (class "Default")
      (node (ref "U5") (pin "28") (pinfunction "PD2/SYNC/ASYNC/OC0C/RXD0_28") (pintype "bidirectional"))
    )
    (net (code "268") (name "unconnected-(U5A-PD3{slash}SYNC{slash}OC0D{slash}TXD0-Pad29)") (class "Default")
      (node (ref "U5") (pin "29") (pinfunction "PD3/SYNC/OC0D/TXD0_29") (pintype "bidirectional"))
    )
    (net (code "269") (name "unconnected-(U5A-PD4{slash}SYNC{slash}OC1A{slash}~{SS}-Pad30)") (class "Default")
      (node (ref "U5") (pin "30") (pinfunction "PD4/SYNC/OC1A/~{SS}_30") (pintype "bidirectional"))
    )
    (net (code "270") (name "unconnected-(U5A-PD5{slash}SYNC{slash}OC1B{slash}XCK1{slash}MOSI-Pad31)") (class "Default")
      (node (ref "U5") (pin "31") (pinfunction "PD5/SYNC/OC1B/XCK1/MOSI_31") (pintype "bidirectional"))
    )
    (net (code "271") (name "unconnected-(U5A-PD6{slash}SYNC{slash}RXD1{slash}MISO-Pad32)") (class "Default")
      (node (ref "U5") (pin "32") (pinfunction "PD6/SYNC/RXD1/MISO_32") (pintype "bidirectional"))
    )
    (net (code "272") (name "unconnected-(U5A-PD7{slash}SYNC{slash}TXD1{slash}SCK{slash}CLKOUT{slash}EVOUT-Pad33)") (class "Default")
      (node (ref "U5") (pin "33") (pinfunction "PD7/SYNC/TXD1/SCK/CLKOUT/EVOUT_33") (pintype "bidirectional"))
    )
    (net (code "273") (name "unconnected-(U5A-PDI{slash}PDI_DATA-Pad56)") (class "Default")
      (node (ref "U5") (pin "56") (pinfunction "PDI/PDI_DATA_56") (pintype "bidirectional"))
    )
    (net (code "274") (name "unconnected-(U5A-PE0{slash}SYNC{slash}OC0A{slash}SDA-Pad36)") (class "Default")
      (node (ref "U5") (pin "36") (pinfunction "PE0/SYNC/OC0A/SDA_36") (pintype "bidirectional"))
    )
    (net (code "275") (name "unconnected-(U5A-PE1{slash}SYNC{slash}OC0B{slash}XCK0{slash}SCL-Pad37)") (class "Default")
      (node (ref "U5") (pin "37") (pinfunction "PE1/SYNC/OC0B/XCK0/SCL_37") (pintype "bidirectional"))
    )
    (net (code "276") (name "unconnected-(U5A-PE2{slash}SYNC{slash}ASYNC{slash}OC0C{slash}RXD0-Pad38)") (class "Default")
      (node (ref "U5") (pin "38") (pinfunction "PE2/SYNC/ASYNC/OC0C/RXD0_38") (pintype "bidirectional"))
    )
    (net (code "277") (name "unconnected-(U5A-PE3{slash}SYNC{slash}OC0D{slash}TXD0-Pad39)") (class "Default")
      (node (ref "U5") (pin "39") (pinfunction "PE3/SYNC/OC0D/TXD0_39") (pintype "bidirectional"))
    )
    (net (code "278") (name "unconnected-(U5A-PE4{slash}SYNC{slash}OC1A{slash}~{SS}-Pad40)") (class "Default")
      (node (ref "U5") (pin "40") (pinfunction "PE4/SYNC/OC1A/~{SS}_40") (pintype "bidirectional"))
    )
    (net (code "279") (name "unconnected-(U5A-PE5{slash}SYNC{slash}OC1B{slash}XCK1{slash}MOSI-Pad41)") (class "Default")
      (node (ref "U5") (pin "41") (pinfunction "PE5/SYNC/OC1B/XCK1/MOSI_41") (pintype "bidirectional"))
    )
    (net (code "280") (name "unconnected-(U5A-PE6{slash}SYNC{slash}RXD1{slash}MISO{slash}TOSC2-Pad42)") (class "Default")
      (node (ref "U5") (pin "42") (pinfunction "PE6/SYNC/RXD1/MISO/TOSC2_42") (pintype "bidirectional"))
    )
    (net (code "281") (name "unconnected-(U5A-PE7{slash}SYNC{slash}TXD1{slash}SCK{slash}CLKOUT{slash}EVOUT{slash}TOSC1-Pad43)") (class "Default")
      (node (ref "U5") (pin "43") (pinfunction "PE7/SYNC/TXD1/SCK/CLKOUT/EVOUT/TOSC1_43") (pintype "bidirectional"))
    )
    (net (code "282") (name "unconnected-(U5A-PF0{slash}SYNC{slash}OC0A-Pad46)") (class "Default")
      (node (ref "U5") (pin "46") (pinfunction "PF0/SYNC/OC0A_46") (pintype "bidirectional"))
    )
    (net (code "283") (name "unconnected-(U5A-PF1{slash}SYNC{slash}OC0B{slash}XCK0-Pad47)") (class "Default")
      (node (ref "U5") (pin "47") (pinfunction "PF1/SYNC/OC0B/XCK0_47") (pintype "bidirectional"))
    )
    (net (code "284") (name "unconnected-(U5A-PF2{slash}SYNC{slash}ASYNC{slash}OC0C{slash}RXD0-Pad48)") (class "Default")
      (node (ref "U5") (pin "48") (pinfunction "PF2/SYNC/ASYNC/OC0C/RXD0_48") (pintype "bidirectional"))
    )
    (net (code "285") (name "unconnected-(U5A-PF3{slash}SYNC{slash}OC0D{slash}TXD0-Pad49)") (class "Default")
      (node (ref "U5") (pin "49") (pinfunction "PF3/SYNC/OC0D/TXD0_49") (pintype "bidirectional"))
    )
    (net (code "286") (name "unconnected-(U5A-PF4{slash}SYNC-Pad50)") (class "Default")
      (node (ref "U5") (pin "50") (pinfunction "PF4/SYNC_50") (pintype "bidirectional"))
    )
    (net (code "287") (name "unconnected-(U5A-PF5{slash}SYNC-Pad51)") (class "Default")
      (node (ref "U5") (pin "51") (pinfunction "PF5/SYNC_51") (pintype "bidirectional"))
    )
    (net (code "288") (name "unconnected-(U5A-PF6{slash}SYNC-Pad54)") (class "Default")
      (node (ref "U5") (pin "54") (pinfunction "PF6/SYNC_54") (pintype "bidirectional"))
    )
    (net (code "289") (name "unconnected-(U5A-PF7{slash}SYNC-Pad55)") (class "Default")
      (node (ref "U5") (pin "55") (pinfunction "PF7/SYNC_55") (pintype "bidirectional"))
    )
    (net (code "290") (name "unconnected-(U5A-PR0{slash}SYNC{slash}XTAL2-Pad58)") (class "Default")
      (node (ref "U5") (pin "58") (pinfunction "PR0/SYNC/XTAL2_58") (pintype "bidirectional"))
    )
    (net (code "291") (name "unconnected-(U5A-PR1{slash}SYNC{slash}XTAL1-Pad59)") (class "Default")
      (node (ref "U5") (pin "59") (pinfunction "PR1/SYNC/XTAL1_59") (pintype "bidirectional"))
    )
    (net (code "292") (name "unconnected-(U5A-~{RESET}{slash}PDI_CLOCK-Pad57)") (class "Default")
      (node (ref "U5") (pin "57") (pinfunction "~{RESET}/PDI_CLOCK_57") (pintype "input"))
    )
    (net (code "293") (name "unconnected-(U5B-AVCC-Pad61)") (class "Default")
      (node (ref "U5") (pin "61") (pinfunction "AVCC_61") (pintype "power_in"))
    )
    (net (code "294") (name "unconnected-(U5B-DAP-Pad65)") (class "Default")
      (node (ref "U5") (pin "65") (pinfunction "DAP_65") (pintype "power_in"))
    )
    (net (code "295") (name "unconnected-(U5B-GND-Pad14)") (class "Default")
      (node (ref "U5") (pin "14") (pinfunction "GND_14") (pintype "power_in"))
    )
    (net (code "296") (name "unconnected-(U5B-GND-Pad24)") (class "Default")
      (node (ref "U5") (pin "24") (pinfunction "GND_24") (pintype "power_in"))
    )
    (net (code "297") (name "unconnected-(U5B-GND-Pad34)") (class "Default")
      (node (ref "U5") (pin "34") (pinfunction "GND_34") (pintype "power_in"))
    )
    (net (code "298") (name "unconnected-(U5B-GND-Pad44)") (class "Default")
      (node (ref "U5") (pin "44") (pinfunction "GND_44") (pintype "power_in"))
    )
    (net (code "299") (name "unconnected-(U5B-GND-Pad52)") (class "Default")
      (node (ref "U5") (pin "52") (pinfunction "GND_52") (pintype "power_in"))
    )
    (net (code "300") (name "unconnected-(U5B-GND-Pad60)") (class "Default")
      (node (ref "U5") (pin "60") (pinfunction "GND_60") (pintype "power_in"))
    )
    (net (code "301") (name "unconnected-(U5B-VCC-Pad15)") (class "Default")
      (node (ref "U5") (pin "15") (pinfunction "VCC_15") (pintype "power_in"))
    )
    (net (code "302") (name "unconnected-(U5B-VCC-Pad25)") (class "Default")
      (node (ref "U5") (pin "25") (pinfunction "VCC_25") (pintype "power_in"))
    )
    (net (code "303") (name "unconnected-(U5B-VCC-Pad35)") (class "Default")
      (node (ref "U5") (pin "35") (pinfunction "VCC_35") (pintype "power_in"))
    )
    (net (code "304") (name "unconnected-(U5B-VCC-Pad45)") (class "Default")
      (node (ref "U5") (pin "45") (pinfunction "VCC_45") (pintype "power_in"))
    )
    (net (code "305") (name "unconnected-(U5B-VCC-Pad53)") (class "Default")
      (node (ref "U5") (pin "53") (pinfunction "VCC_53") (pintype "power_in"))
    )
  )
)
